# FIT_HDMI_X25-29.net
KiCad netlist of a schematic drawn in Altium Designer
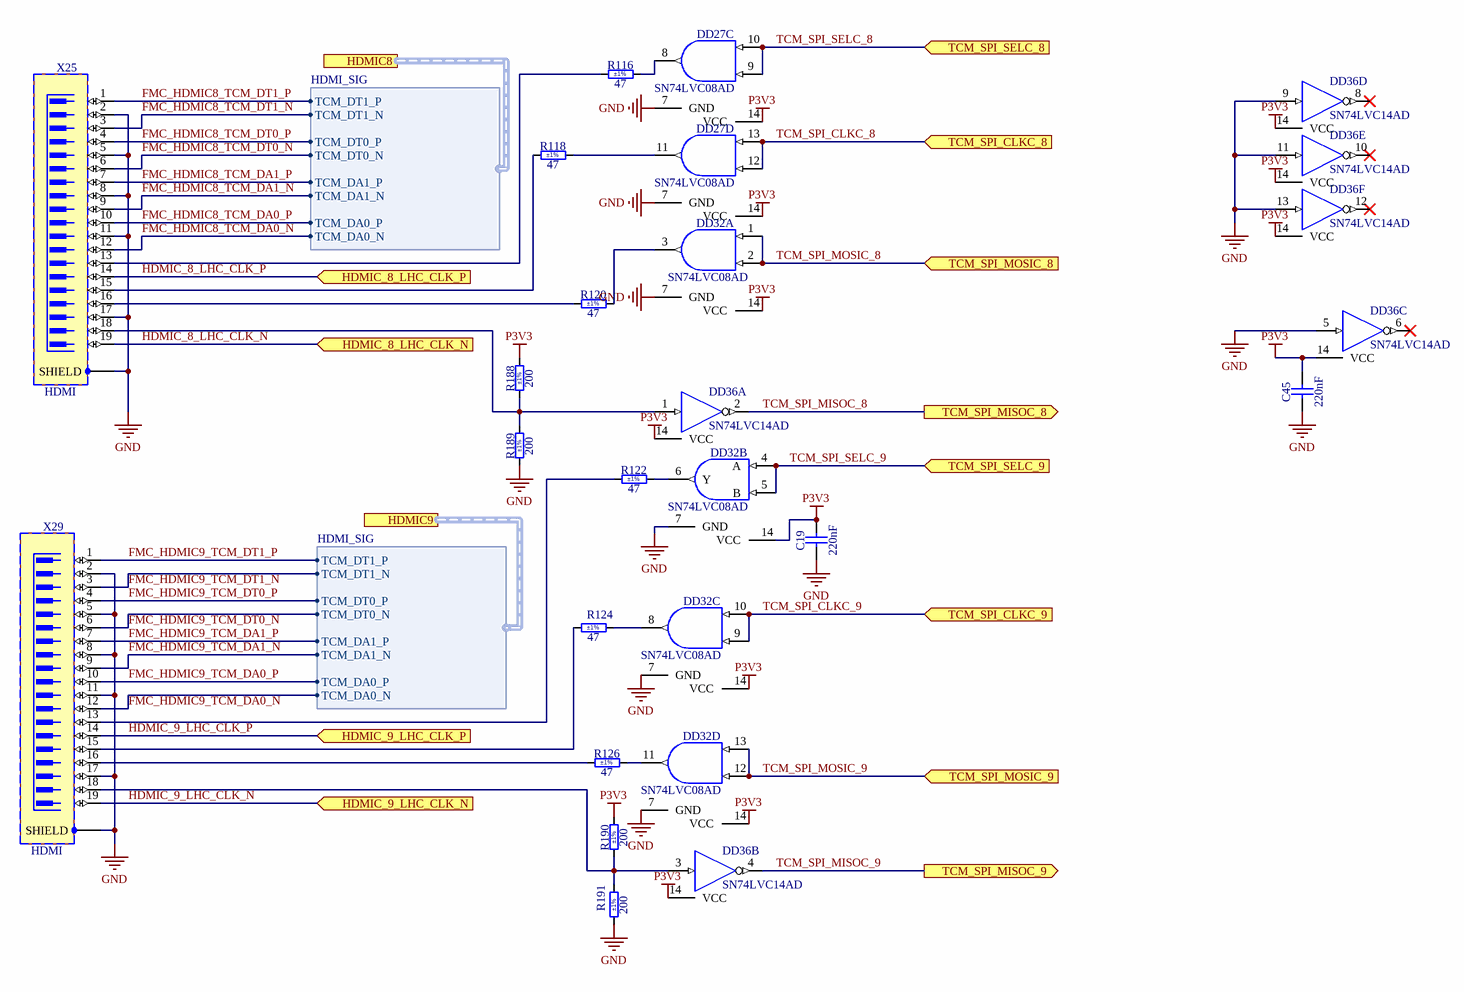
[diagram p0: FIT_HDMI_X25-29.SchDoc]

(export (version "E")
  (design (tool "Eeschema 10.0.6"))
  (components
    (comp (ref "C19")
      (value "220nF")
      (footprint "CAPC2012X135N")
      (description "Non-polarised capacitor")
      (fields
        (field (name "PART NUMBER") "CC0805_220NF_50V_10%_X7R")
        (field (name "VOLTAGE") "50V")
        (field (name "AUTHOR") "CERN DEM JLC")
      )
      (libsource (lib "Capacitors") (part "Capacitor - non polarized"))
    )
    (comp (ref "C45")
      (value "220nF")
      (footprint "CAPC2012X135N")
      (description "Non-polarised capacitor")
      (fields
        (field (name "PART NUMBER") "CC0805_220NF_50V_10%_X7R")
        (field (name "VOLTAGE") "50V")
        (field (name "AUTHOR") "CERN DEM JLC")
      )
      (libsource (lib "Capacitors") (part "Capacitor - non polarized"))
    )
    (comp (ref "DD27")
      (value "SN74LVC08AD")
      (footprint "SOIC127P600X175-14N")
      (description "Quad 2-Input AND Gate")
      (fields (field (name "MANUFACTURER") "TEXAS INSTRUMENTS") (field (name "AUTHOR") "CERN DEM JLC"))
      (libsource (lib "ICs And Semiconductors") (part "7408"))
    )
    (comp (ref "DD32")
      (value "SN74LVC08AD")
      (footprint "SOIC127P600X175-14N")
      (description "Quad 2-Input AND Gate")
      (fields (field (name "MANUFACTURER") "TEXAS INSTRUMENTS") (field (name "AUTHOR") "CERN DEM JLC"))
      (libsource (lib "ICs And Semiconductors") (part "7408"))
    )
    (comp (ref "DD36")
      (value "SN74LVC14AD")
      (footprint "SOIC127P600X175-14N")
      (description "Hex Schmitt-Trigger Inverter")
      (fields (field (name "MANUFACTURER") "TEXAS INSTRUMENTS") (field (name "AUTHOR") "CERN DEM JMW"))
      (libsource (lib "ICs And Semiconductors") (part "7414"))
    )
    (comp (ref "R116")
      (value "47")
      (footprint "RESC2012X60N")
      (description "Resistor - 1%")
      (fields
        (field (name "TOLERANCE") "±1%")
        (field (name "PART NUMBER") "R0805_47R_1%_0.125W_100PPM")
        (field (name "POWER") "0.125W")
        (field (name "AUTHOR") "CERN DEM JLC")
      )
      (libsource (lib "Resistors") (part "Resistor - 1%"))
    )
    (comp (ref "R118")
      (value "47")
      (footprint "RESC2012X60N")
      (description "Resistor - 1%")
      (fields
        (field (name "TOLERANCE") "±1%")
        (field (name "PART NUMBER") "R0805_47R_1%_0.125W_100PPM")
        (field (name "POWER") "0.125W")
        (field (name "AUTHOR") "CERN DEM JLC")
      )
      (libsource (lib "Resistors") (part "Resistor - 1%"))
    )
    (comp (ref "R120")
      (value "47")
      (footprint "RESC2012X60N")
      (description "Resistor - 1%")
      (fields
        (field (name "TOLERANCE") "±1%")
        (field (name "PART NUMBER") "R0805_47R_1%_0.125W_100PPM")
        (field (name "POWER") "0.125W")
        (field (name "AUTHOR") "CERN DEM JLC")
      )
      (libsource (lib "Resistors") (part "Resistor - 1%"))
    )
    (comp (ref "R122")
      (value "47")
      (footprint "RESC2012X60N")
      (description "Resistor - 1%")
      (fields
        (field (name "TOLERANCE") "±1%")
        (field (name "PART NUMBER") "R0805_47R_1%_0.125W_100PPM")
        (field (name "POWER") "0.125W")
        (field (name "AUTHOR") "CERN DEM JLC")
      )
      (libsource (lib "Resistors") (part "Resistor - 1%"))
    )
    (comp (ref "R124")
      (value "47")
      (footprint "RESC2012X60N")
      (description "Resistor - 1%")
      (fields
        (field (name "TOLERANCE") "±1%")
        (field (name "PART NUMBER") "R0805_47R_1%_0.125W_100PPM")
        (field (name "POWER") "0.125W")
        (field (name "AUTHOR") "CERN DEM JLC")
      )
      (libsource (lib "Resistors") (part "Resistor - 1%"))
    )
    (comp (ref "R126")
      (value "47")
      (footprint "RESC2012X60N")
      (description "Resistor - 1%")
      (fields
        (field (name "TOLERANCE") "±1%")
        (field (name "PART NUMBER") "R0805_47R_1%_0.125W_100PPM")
        (field (name "POWER") "0.125W")
        (field (name "AUTHOR") "CERN DEM JLC")
      )
      (libsource (lib "Resistors") (part "Resistor - 1%"))
    )
    (comp (ref "R188")
      (value "200")
      (footprint "RESC2012X60N")
      (description "Resistor - 1%")
      (fields
        (field (name "TOLERANCE") "±1%")
        (field (name "PART NUMBER") "R0805_200R_1%_0.125W_100PPM")
        (field (name "POWER") "0.125W")
        (field (name "AUTHOR") "CERN DEM JLC")
      )
      (libsource (lib "Resistors") (part "Resistor - 1%"))
    )
    (comp (ref "R189")
      (value "200")
      (footprint "RESC2012X60N")
      (description "Resistor - 1%")
      (fields
        (field (name "TOLERANCE") "±1%")
        (field (name "PART NUMBER") "R0805_200R_1%_0.125W_100PPM")
        (field (name "POWER") "0.125W")
        (field (name "AUTHOR") "CERN DEM JLC")
      )
      (libsource (lib "Resistors") (part "Resistor - 1%"))
    )
    (comp (ref "R190")
      (value "200")
      (footprint "RESC2012X60N")
      (description "Resistor - 1%")
      (fields
        (field (name "TOLERANCE") "±1%")
        (field (name "PART NUMBER") "R0805_200R_1%_0.125W_100PPM")
        (field (name "POWER") "0.125W")
        (field (name "AUTHOR") "CERN DEM JLC")
      )
      (libsource (lib "Resistors") (part "Resistor - 1%"))
    )
    (comp (ref "R191")
      (value "200")
      (footprint "RESC2012X60N")
      (description "Resistor - 1%")
      (fields
        (field (name "TOLERANCE") "±1%")
        (field (name "PART NUMBER") "R0805_200R_1%_0.125W_100PPM")
        (field (name "POWER") "0.125W")
        (field (name "AUTHOR") "CERN DEM JLC")
      )
      (libsource (lib "Resistors") (part "Resistor - 1%"))
    )
    (comp (ref "X25")
      (value "HDMI")
      (footprint "TYCO_2007435-1")
      (description "Connector HDMI 19 Male + 1 Shield")
      (fields
        (field (name "PART NUMBER") "TYCO_2007435-1")
        (field (name "MANUFACTURER") "TYCO ELECTRONICS")
        (field (name "AUTHOR") "CERN DEM MR")
      )
      (libsource (lib "Connectors") (part "Connector HDMI 19 Male + 1 Shield"))
    )
    (comp (ref "X29")
      (value "HDMI")
      (footprint "TYCO_2007435-1")
      (description "Connector HDMI 19 Male + 1 Shield")
      (fields
        (field (name "PART NUMBER") "TYCO_2007435-1")
        (field (name "MANUFACTURER") "TYCO ELECTRONICS")
        (field (name "AUTHOR") "CERN DEM MR")
      )
      (libsource (lib "Connectors") (part "Connector HDMI 19 Male + 1 Shield"))
    )
  )
  (nets
    (net (code "3") (name "/FMC_HDMIC8_TCM_DA0_P") (class "Default")
      (node (ref "X25") (pin "10") (pinfunction "10_10") (pintype "bidirectional"))
    )
    (net (code "5") (name "/FMC_HDMIC8_TCM_DA1_P") (class "Default")
      (node (ref "X25") (pin "7") (pinfunction "7_7") (pintype "bidirectional"))
    )
    (net (code "6") (name "/FMC_HDMIC8_TCM_DT0_N") (class "Default")
      (node (ref "X25") (pin "6") (pinfunction "6_6") (pintype "bidirectional"))
    )
    (net (code "7") (name "/FMC_HDMIC8_TCM_DT0_P") (class "Default")
      (node (ref "X25") (pin "4") (pinfunction "4_4") (pintype "bidirectional"))
    )
    (net (code "8") (name "/FMC_HDMIC8_TCM_DT1_N") (class "Default")
      (node (ref "X25") (pin "3") (pinfunction "3_3") (pintype "bidirectional"))
    )
    (net (code "9") (name "/FMC_HDMIC8_TCM_DT1_P") (class "Default")
      (node (ref "X25") (pin "1") (pinfunction "1_1") (pintype "bidirectional"))
    )
    (net (code "10") (name "/FMC_HDMIC9_TCM_DA0_N") (class "Default")
      (node (ref "X29") (pin "12") (pinfunction "12_12") (pintype "bidirectional"))
    )
    (net (code "11") (name "/FMC_HDMIC9_TCM_DA0_P") (class "Default")
      (node (ref "X29") (pin "10") (pinfunction "10_10") (pintype "bidirectional"))
    )
    (net (code "13") (name "/FMC_HDMIC9_TCM_DA1_P") (class "Default")
      (node (ref "X29") (pin "7") (pinfunction "7_7") (pintype "bidirectional"))
    )
    (net (code "14") (name "/FMC_HDMIC9_TCM_DT0_N") (class "Default")
      (node (ref "X29") (pin "6") (pinfunction "6_6") (pintype "bidirectional"))
    )
    (net (code "15") (name "/FMC_HDMIC9_TCM_DT0_P") (class "Default")
      (node (ref "X29") (pin "4") (pinfunction "4_4") (pintype "bidirectional"))
    )
    (net (code "16") (name "/FMC_HDMIC9_TCM_DT1_N") (class "Default")
      (node (ref "X29") (pin "3") (pinfunction "3_3") (pintype "bidirectional"))
    )
    (net (code "17") (name "/FMC_HDMIC9_TCM_DT1_P") (class "Default")
      (node (ref "X29") (pin "1") (pinfunction "1_1") (pintype "bidirectional"))
    )
    (net (code "18") (name "/HDMIC_8_LHC_CLK_N") (class "Default")
      (node (ref "X25") (pin "19") (pinfunction "19_19") (pintype "bidirectional"))
    )
    (net (code "19") (name "/HDMIC_8_LHC_CLK_P") (class "Default")
      (node (ref "X25") (pin "14") (pinfunction "14_14") (pintype "bidirectional"))
    )
    (net (code "20") (name "/HDMIC_9_LHC_CLK_N") (class "Default")
      (node (ref "X29") (pin "19") (pinfunction "19_19") (pintype "bidirectional"))
    )
    (net (code "21") (name "/HDMIC_9_LHC_CLK_P") (class "Default")
      (node (ref "X29") (pin "14") (pinfunction "14_14") (pintype "bidirectional"))
    )
    (net (code "22") (name "/TCM_SPI_CLKC_8") (class "Default")
      (node (ref "DD27") (pin "12") (pinfunction "B_12") (pintype "input"))
      (node (ref "DD27") (pin "13") (pinfunction "A_13") (pintype "input"))
    )
    (net (code "23") (name "/TCM_SPI_CLKC_9") (class "Default")
      (node (ref "DD32") (pin "10") (pinfunction "A_10") (pintype "input"))
      (node (ref "DD32") (pin "9") (pinfunction "B_9") (pintype "input"))
    )
    (net (code "24") (name "/TCM_SPI_MISOC_8") (class "Default")
      (node (ref "DD36") (pin "2") (pinfunction "OUT_2") (pintype "output"))
    )
    (net (code "25") (name "/TCM_SPI_MISOC_9") (class "Default")
      (node (ref "DD36") (pin "4") (pinfunction "OUT_4") (pintype "output"))
    )
    (net (code "26") (name "/TCM_SPI_MOSIC_8") (class "Default")
      (node (ref "DD32") (pin "1") (pinfunction "A_1") (pintype "input"))
      (node (ref "DD32") (pin "2") (pinfunction "B_2") (pintype "input"))
    )
    (net (code "27") (name "/TCM_SPI_MOSIC_9") (class "Default")
      (node (ref "DD32") (pin "12") (pinfunction "B_12") (pintype "input"))
      (node (ref "DD32") (pin "13") (pinfunction "A_13") (pintype "input"))
    )
    (net (code "28") (name "/TCM_SPI_SELC_8") (class "Default")
      (node (ref "DD27") (pin "10") (pinfunction "A_10") (pintype "input"))
      (node (ref "DD27") (pin "9") (pinfunction "B_9") (pintype "input"))
    )
    (net (code "29") (name "/TCM_SPI_SELC_9") (class "Default")
      (node (ref "DD32") (pin "4") (pinfunction "A_4") (pintype "input"))
      (node (ref "DD32") (pin "5") (pinfunction "B_5") (pintype "input"))
    )
    (net (code "31") (name "GND") (class "Default")
      (node (ref "C19") (pin "1") (pinfunction "1_1") (pintype "passive"))
      (node (ref "C45") (pin "1") (pinfunction "1_1") (pintype "passive"))
      (node (ref "DD27") (pin "7") (pinfunction "GND_7") (pintype "power_in"))
      (node (ref "DD32") (pin "7") (pinfunction "GND_7") (pintype "power_in"))
      (node (ref "DD36") (pin "11") (pinfunction "IN_11") (pintype "input"))
      (node (ref "DD36") (pin "13") (pinfunction "IN_13") (pintype "input"))
      (node (ref "DD36") (pin "5") (pinfunction "IN_5") (pintype "input"))
      (node (ref "DD36") (pin "7") (pinfunction "GND_7") (pintype "power_in"))
      (node (ref "DD36") (pin "9") (pinfunction "IN_9") (pintype "input"))
      (node (ref "R189") (pin "1") (pinfunction "1_1") (pintype "passive"))
      (node (ref "R191") (pin "1") (pinfunction "1_1") (pintype "passive"))
      (node (ref "X25") (pin "11") (pinfunction "11_11") (pintype "bidirectional"))
      (node (ref "X25") (pin "17") (pinfunction "17_17") (pintype "bidirectional"))
      (node (ref "X25") (pin "2") (pinfunction "2_2") (pintype "bidirectional"))
      (node (ref "X25") (pin "5") (pinfunction "5_5") (pintype "bidirectional"))
      (node (ref "X25") (pin "8") (pinfunction "8_8") (pintype "bidirectional"))
      (node (ref "X25") (pin "SHIELD") (pinfunction "SHIELD_SHIELD") (pintype "power_in"))
      (node (ref "X29") (pin "11") (pinfunction "11_11") (pintype "bidirectional"))
      (node (ref "X29") (pin "17") (pinfunction "17_17") (pintype "bidirectional"))
      (node (ref "X29") (pin "2") (pinfunction "2_2") (pintype "bidirectional"))
      (node (ref "X29") (pin "5") (pinfunction "5_5") (pintype "bidirectional"))
      (node (ref "X29") (pin "8") (pinfunction "8_8") (pintype "bidirectional"))
      (node (ref "X29") (pin "SHIELD") (pinfunction "SHIELD_SHIELD") (pintype "power_in"))
    )
    (net (code "32") (name "Net-(DD27C-Y)") (class "Default")
      (node (ref "DD27") (pin "8") (pinfunction "Y_8") (pintype "output"))
      (node (ref "R116") (pin "2") (pinfunction "2_2") (pintype "passive"))
    )
    (net (code "33") (name "Net-(DD27D-Y)") (class "Default")
      (node (ref "DD27") (pin "11") (pinfunction "Y_11") (pintype "output"))
      (node (ref "R118") (pin "2") (pinfunction "2_2") (pintype "passive"))
    )
    (net (code "34") (name "Net-(DD32A-Y)") (class "Default")
      (node (ref "DD32") (pin "3") (pinfunction "Y_3") (pintype "output"))
      (node (ref "R120") (pin "2") (pinfunction "2_2") (pintype "passive"))
    )
    (net (code "35") (name "Net-(DD32B-Y)") (class "Default")
      (node (ref "DD32") (pin "6") (pinfunction "Y_6") (pintype "output"))
      (node (ref "R122") (pin "2") (pinfunction "2_2") (pintype "passive"))
    )
    (net (code "36") (name "Net-(DD32C-Y)") (class "Default")
      (node (ref "DD32") (pin "8") (pinfunction "Y_8") (pintype "output"))
      (node (ref "R124") (pin "2") (pinfunction "2_2") (pintype "passive"))
    )
    (net (code "37") (name "Net-(DD32D-Y)") (class "Default")
      (node (ref "DD32") (pin "11") (pinfunction "Y_11") (pintype "output"))
      (node (ref "R126") (pin "2") (pinfunction "2_2") (pintype "passive"))
    )
    (net (code "38") (name "Net-(DD36A-IN)") (class "Default")
      (node (ref "DD36") (pin "1") (pinfunction "IN_1") (pintype "input"))
      (node (ref "R188") (pin "1") (pinfunction "1_1") (pintype "passive"))
      (node (ref "R189") (pin "2") (pinfunction "2_2") (pintype "passive"))
      (node (ref "X25") (pin "18") (pinfunction "18_18") (pintype "bidirectional"))
    )
    (net (code "39") (name "Net-(DD36B-IN)") (class "Default")
      (node (ref "DD36") (pin "3") (pinfunction "IN_3") (pintype "input"))
      (node (ref "R190") (pin "1") (pinfunction "1_1") (pintype "passive"))
      (node (ref "R191") (pin "2") (pinfunction "2_2") (pintype "passive"))
      (node (ref "X29") (pin "18") (pinfunction "18_18") (pintype "bidirectional"))
    )
    (net (code "40") (name "Net-(R116-Pad1)") (class "Default")
      (node (ref "R116") (pin "1") (pinfunction "1_1") (pintype "passive"))
      (node (ref "X25") (pin "13") (pinfunction "13_13") (pintype "bidirectional"))
    )
    (net (code "41") (name "Net-(R118-Pad1)") (class "Default")
      (node (ref "R118") (pin "1") (pinfunction "1_1") (pintype "passive"))
      (node (ref "X25") (pin "15") (pinfunction "15_15") (pintype "bidirectional"))
    )
    (net (code "42") (name "Net-(R120-Pad1)") (class "Default")
      (node (ref "R120") (pin "1") (pinfunction "1_1") (pintype "passive"))
      (node (ref "X25") (pin "16") (pinfunction "16_16") (pintype "bidirectional"))
    )
    (net (code "43") (name "Net-(R122-Pad1)") (class "Default")
      (node (ref "R122") (pin "1") (pinfunction "1_1") (pintype "passive"))
      (node (ref "X29") (pin "13") (pinfunction "13_13") (pintype "bidirectional"))
    )
    (net (code "44") (name "Net-(R124-Pad1)") (class "Default")
      (node (ref "R124") (pin "1") (pinfunction "1_1") (pintype "passive"))
      (node (ref "X29") (pin "15") (pinfunction "15_15") (pintype "bidirectional"))
    )
    (net (code "45") (name "Net-(R126-Pad1)") (class "Default")
      (node (ref "R126") (pin "1") (pinfunction "1_1") (pintype "passive"))
      (node (ref "X29") (pin "16") (pinfunction "16_16") (pintype "bidirectional"))
    )
    (net (code "46") (name "P3V3") (class "Default")
      (node (ref "C19") (pin "2") (pinfunction "2_2") (pintype "passive"))
      (node (ref "C45") (pin "2") (pinfunction "2_2") (pintype "passive"))
      (node (ref "DD27") (pin "14") (pinfunction "VCC_14") (pintype "power_in"))
      (node (ref "DD32") (pin "14") (pinfunction "VCC_14") (pintype "power_in"))
      (node (ref "DD36") (pin "14") (pinfunction "VCC_14") (pintype "power_in"))
      (node (ref "R188") (pin "2") (pinfunction "2_2") (pintype "passive"))
      (node (ref "R190") (pin "2") (pinfunction "2_2") (pintype "passive"))
    )
    (net (code "47") (name "unconnected-(DD36C-OUT-Pad6)") (class "Default")
      (node (ref "DD36") (pin "6") (pinfunction "OUT_6") (pintype "output+no_connect"))
    )
    (net (code "48") (name "unconnected-(DD36D-OUT-Pad8)") (class "Default")
      (node (ref "DD36") (pin "8") (pinfunction "OUT_8") (pintype "output+no_connect"))
    )
    (net (code "49") (name "unconnected-(DD36E-OUT-Pad10)") (class "Default")
      (node (ref "DD36") (pin "10") (pinfunction "OUT_10") (pintype "output+no_connect"))
    )
    (net (code "50") (name "unconnected-(DD36F-OUT-Pad12)") (class "Default")
      (node (ref "DD36") (pin "12") (pinfunction "OUT_12") (pintype "output+no_connect"))
    )
    (net (code "51") (name "unconnected-(X25-Pad9)") (class "Default")
      (node (ref "X25") (pin "9") (pinfunction "9_9") (pintype "bidirectional"))
    )
    (net (code "52") (name "unconnected-(X25-Pad12)") (class "Default")
      (node (ref "X25") (pin "12") (pinfunction "12_12") (pintype "bidirectional"))
    )
    (net (code "53") (name "unconnected-(X29-Pad9)") (class "Default")
      (node (ref "X29") (pin "9") (pinfunction "9_9") (pintype "bidirectional"))
    )
  )
)
